# HM-ES-TX-WM_IEC_v1p0.net
KiCad netlist of a schematic drawn in EAGLE
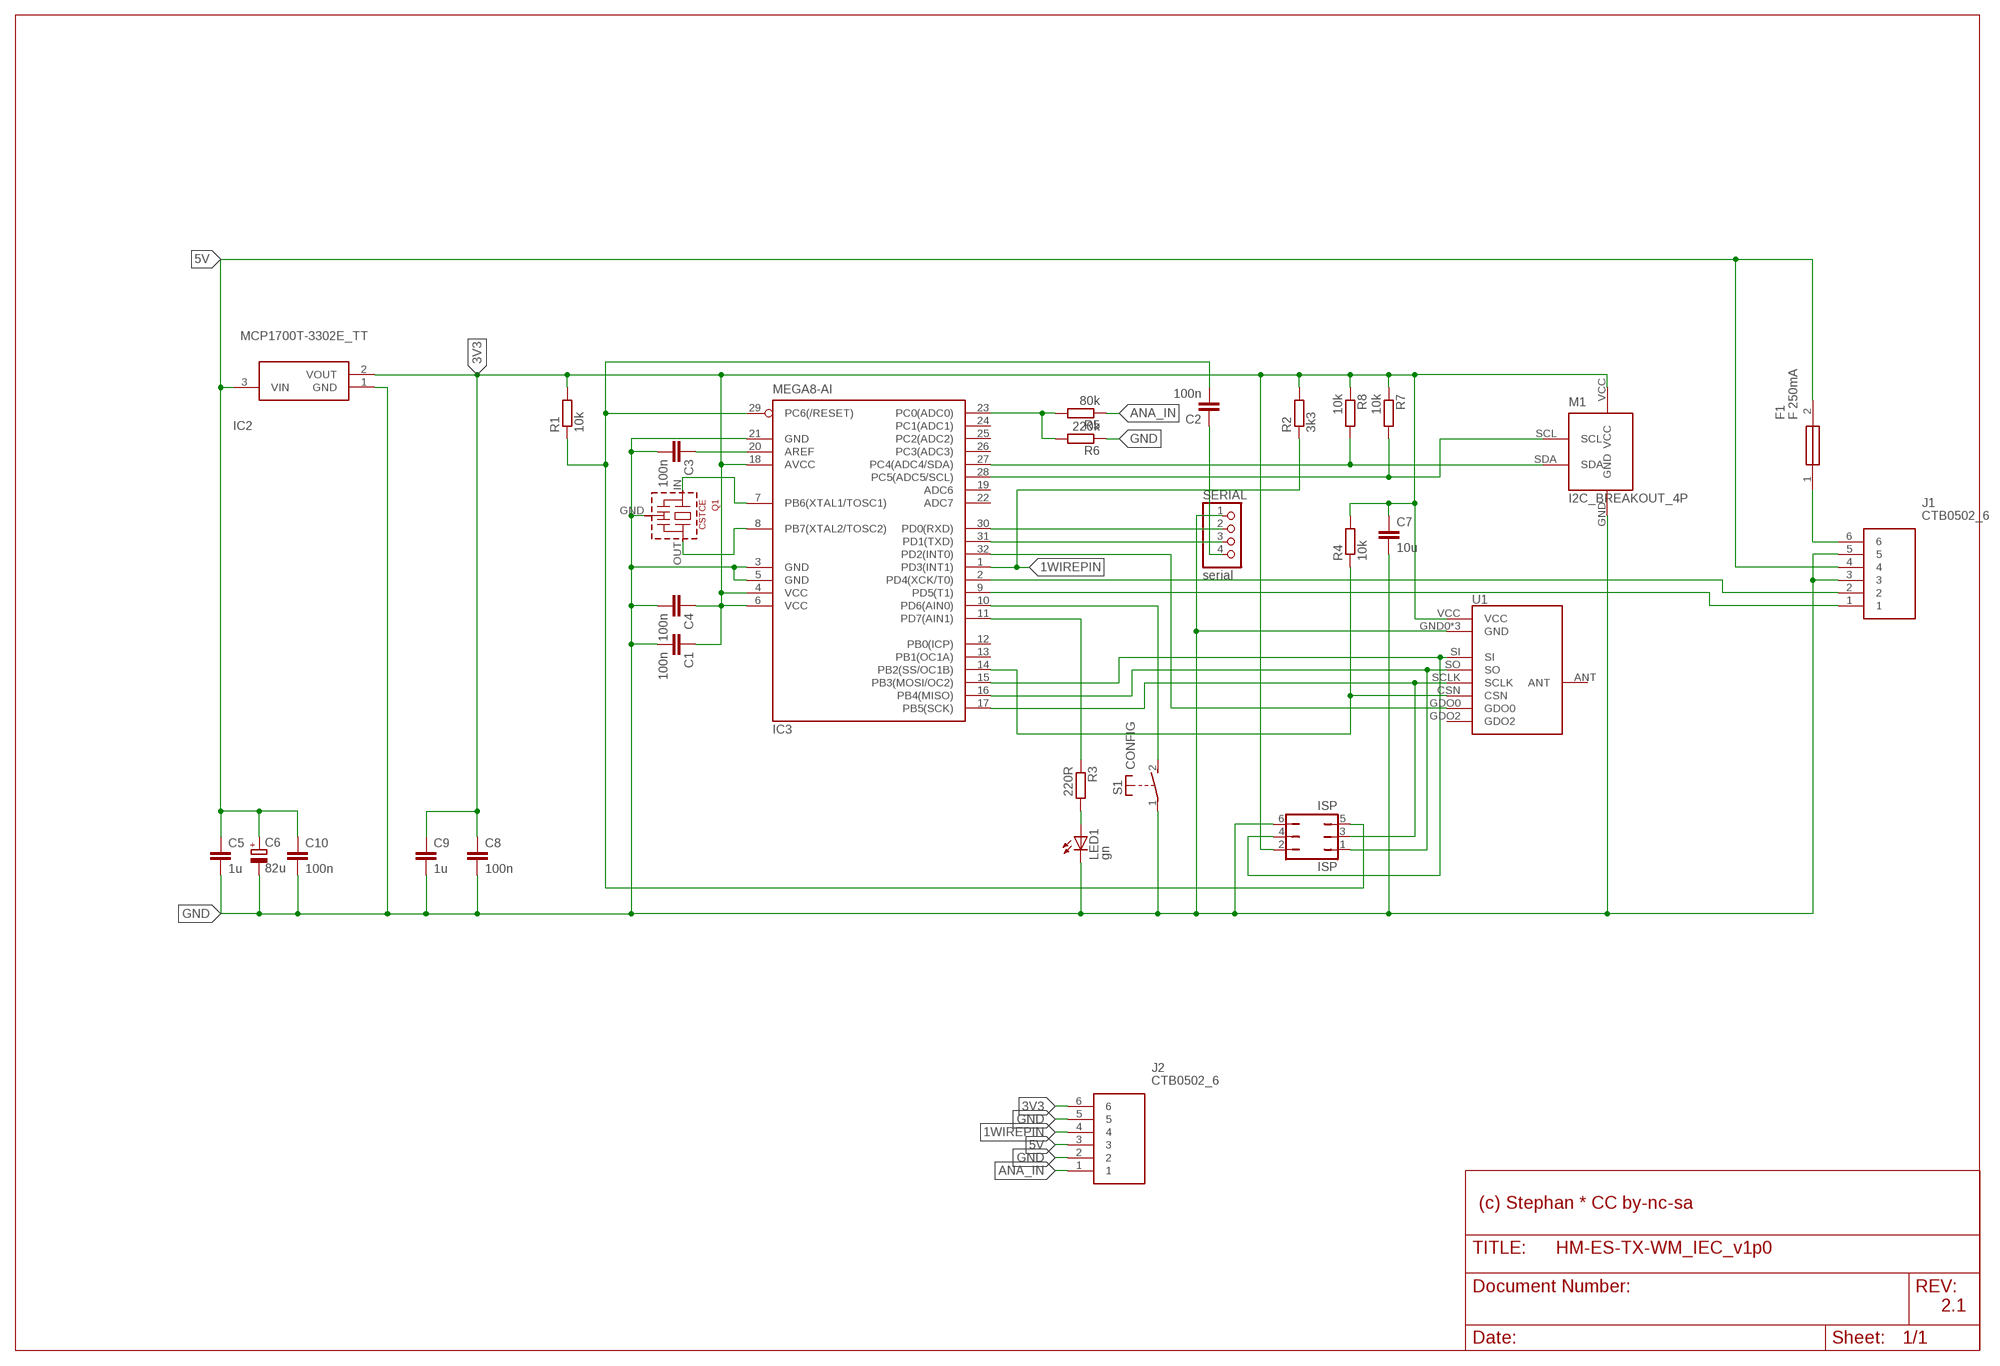
[diagram p0: schematic, sheet 1]

(export (version "E")
  (design (tool "Eeschema 10.0.6"))
  (components
    (comp (ref "C1")
      (value "100n")
      (footprint "eagle-import:C0805K")
      (libsource (lib "eagle-import") (part "C-EUC0805K"))
    )
    (comp (ref "C2")
      (value "100n")
      (footprint "eagle-import:C0805K")
      (libsource (lib "eagle-import") (part "C-EUC0805K"))
    )
    (comp (ref "C3")
      (value "100n")
      (footprint "eagle-import:C0805K")
      (libsource (lib "eagle-import") (part "C-EUC0805K"))
    )
    (comp (ref "C4")
      (value "100n")
      (footprint "eagle-import:C0805K")
      (libsource (lib "eagle-import") (part "C-EUC0805K"))
    )
    (comp (ref "C5")
      (value "1u")
      (footprint "eagle-import:C0805K")
      (libsource (lib "eagle-import") (part "C-EUC0805K"))
    )
    (comp (ref "C6")
      (value "82u")
      (footprint "eagle-import:SANYO-OSCON_SMD_C6")
      (libsource (lib "eagle-import") (part "CPOL-EUSANYO_SMD_C6"))
    )
    (comp (ref "C7")
      (value "10u")
      (footprint "eagle-import:C0805K")
      (libsource (lib "eagle-import") (part "C-EUC0805K"))
    )
    (comp (ref "C8")
      (value "100n")
      (footprint "eagle-import:C0805K")
      (libsource (lib "eagle-import") (part "C-EUC0805K"))
    )
    (comp (ref "C9")
      (value "1u")
      (footprint "eagle-import:C0805K")
      (libsource (lib "eagle-import") (part "C-EUC0805K"))
    )
    (comp (ref "C10")
      (value "100n")
      (footprint "eagle-import:C0805K")
      (libsource (lib "eagle-import") (part "C-EUC0805K"))
    )
    (comp (ref "F1")
      (value "F 250mA")
      (footprint "eagle-import:FUSC6125X279N")
      (fields (field (name "ARROW_PART_NUMBER") "0679H1000-05"))
      (libsource (lib "eagle-import") (part "0679H1000-05"))
    )
    (comp (ref "IC2")
      (value "MCP1700T-3302E_TT")
      (footprint "eagle-import:SOT95P237X112-3N")
      (fields
        (field (name "ARROW_PART_NUMBER") "MCP1700T-5002E/TT")
        (field (name "MOUSER_PART_NUMBER") "579-MCP1700T5002E/TT")
      )
      (libsource (lib "eagle-import") (part "MCP1700T-5002E_TT"))
    )
    (comp (ref "IC3")
      (value "MEGA8-AI")
      (footprint "eagle-import:TQFP32-08")
      (fields (field (name "MPN") "ATMEGA8-16AU"))
      (libsource (lib "eagle-import") (part "MEGA8-AI"))
    )
    (comp (ref "ISP")
      (value "ISP")
      (footprint "eagle-import:JP3Q")
      (libsource (lib "eagle-import") (part "JP3Q"))
    )
    (comp (ref "J1")
      (value "CTB0502_6")
      (footprint "eagle-import:CTB05026")
      (fields (field (name "MANUFACTURER_PART_NUMBER") "CTB0502/6"))
      (libsource (lib "eagle-import") (part "CTB0502_6"))
    )
    (comp (ref "J2")
      (value "CTB0502_6")
      (footprint "eagle-import:CTB05026")
      (fields (field (name "MANUFACTURER_PART_NUMBER") "CTB0502/6"))
      (libsource (lib "eagle-import") (part "CTB0502_6"))
    )
    (comp (ref "LED1")
      (value "gn")
      (footprint "eagle-import:CHIPLED_0805")
      (libsource (lib "eagle-import") (part "LEDCHIPLED_0805"))
    )
    (comp (ref "M1")
      (value "I2C_BREAKOUT_4P")
      (footprint "eagle-import:I2C_BREAKOUT_4P")
      (libsource (lib "eagle-import") (part "I2C_BREAKOUT_4P"))
    )
    (comp (ref "Q1")
      (value "CSTCE")
      (footprint "eagle-import:CSTCE")
      (libsource (lib "eagle-import") (part "CSTCE"))
    )
    (comp (ref "R1")
      (value "10k")
      (footprint "eagle-import:R0805W")
      (libsource (lib "eagle-import") (part "R-EU_R0805W"))
    )
    (comp (ref "R2")
      (value "3k3")
      (footprint "eagle-import:R0805W")
      (libsource (lib "eagle-import") (part "R-EU_R0805W"))
    )
    (comp (ref "R3")
      (value "220R")
      (footprint "eagle-import:R0805W")
      (libsource (lib "eagle-import") (part "R-EU_R0805W"))
    )
    (comp (ref "R4")
      (value "10k")
      (footprint "eagle-import:R0805W")
      (libsource (lib "eagle-import") (part "R-EU_R0805W"))
    )
    (comp (ref "R5")
      (value "80k")
      (footprint "eagle-import:R0805W")
      (libsource (lib "eagle-import") (part "R-EU_R0805W"))
    )
    (comp (ref "R6")
      (value "220k")
      (footprint "eagle-import:R0805W")
      (libsource (lib "eagle-import") (part "R-EU_R0805W"))
    )
    (comp (ref "R7")
      (value "10k")
      (footprint "eagle-import:R0805W")
      (libsource (lib "eagle-import") (part "R-EU_R0805W"))
    )
    (comp (ref "R8")
      (value "10k")
      (footprint "eagle-import:R0805W")
      (libsource (lib "eagle-import") (part "R-EU_R0805W"))
    )
    (comp (ref "S1")
      (value "CONFIG")
      (footprint "eagle-import:SMDSWITCH6X4")
      (libsource (lib "eagle-import") (part "SMDSWITCH6X4"))
    )
    (comp (ref "SERIAL")
      (value "serial")
      (footprint "eagle-import:1X04")
      (libsource (lib "eagle-import") (part "PINHD-1X4"))
    )
    (comp (ref "U1")
      (value "CC1101SMD")
      (footprint "eagle-import:CC1101-SMD")
      (libsource (lib "eagle-import") (part "CC1101SMD"))
    )
  )
  (nets
    (net (code "1") (name "1WIREPIN") (class "Default")
      (node (ref "IC3") (pin "1") (pinfunction "PD3(INT1)_1") (pintype "bidirectional"))
      (node (ref "J2") (pin "4") (pinfunction "4_4") (pintype "bidirectional"))
      (node (ref "R2") (pin "1") (pinfunction "1_1") (pintype "passive"))
    )
    (net (code "2") (name "3V3") (class "Default")
      (node (ref "C1") (pin "1") (pinfunction "1_1") (pintype "passive"))
      (node (ref "C4") (pin "1") (pinfunction "1_1") (pintype "passive"))
      (node (ref "C7") (pin "1") (pinfunction "1_1") (pintype "passive"))
      (node (ref "C8") (pin "1") (pinfunction "1_1") (pintype "passive"))
      (node (ref "C9") (pin "1") (pinfunction "1_1") (pintype "passive"))
      (node (ref "IC2") (pin "2") (pinfunction "VOUT_2") (pintype "bidirectional"))
      (node (ref "IC3") (pin "18") (pinfunction "AVCC_18") (pintype "power_in"))
      (node (ref "IC3") (pin "4") (pinfunction "VCC_4") (pintype "power_in"))
      (node (ref "IC3") (pin "6") (pinfunction "VCC_6") (pintype "power_in"))
      (node (ref "ISP") (pin "2") (pinfunction "2_2") (pintype "passive"))
      (node (ref "J2") (pin "6") (pinfunction "6_6") (pintype "bidirectional"))
      (node (ref "M1") (pin "VCC") (pinfunction "VCC_VCC") (pintype "power_in"))
      (node (ref "R1") (pin "2") (pinfunction "2_2") (pintype "passive"))
      (node (ref "R2") (pin "2") (pinfunction "2_2") (pintype "passive"))
      (node (ref "R4") (pin "2") (pinfunction "2_2") (pintype "passive"))
      (node (ref "R7") (pin "1") (pinfunction "1_1") (pintype "passive"))
      (node (ref "R8") (pin "1") (pinfunction "1_1") (pintype "passive"))
      (node (ref "U1") (pin "VCC") (pinfunction "VCC_VCC") (pintype "power_in"))
    )
    (net (code "3") (name "5V") (class "Default")
      (node (ref "C10") (pin "1") (pinfunction "1_1") (pintype "passive"))
      (node (ref "C5") (pin "1") (pinfunction "1_1") (pintype "passive"))
      (node (ref "C6") (pin "+") (pinfunction "+_+") (pintype "passive"))
      (node (ref "F1") (pin "2") (pinfunction "2_2") (pintype "bidirectional"))
      (node (ref "IC2") (pin "3") (pinfunction "VIN_3") (pintype "bidirectional"))
      (node (ref "J1") (pin "4") (pinfunction "4_4") (pintype "bidirectional"))
      (node (ref "J2") (pin "3") (pinfunction "3_3") (pintype "bidirectional"))
    )
    (net (code "4") (name "ANA_IN") (class "Default")
      (node (ref "J2") (pin "1") (pinfunction "1_1") (pintype "bidirectional"))
      (node (ref "R5") (pin "1") (pinfunction "1_1") (pintype "passive"))
    )
    (net (code "5") (name "GND") (class "Default")
      (node (ref "C1") (pin "2") (pinfunction "2_2") (pintype "passive"))
      (node (ref "C10") (pin "2") (pinfunction "2_2") (pintype "passive"))
      (node (ref "C3") (pin "2") (pinfunction "2_2") (pintype "passive"))
      (node (ref "C4") (pin "2") (pinfunction "2_2") (pintype "passive"))
      (node (ref "C5") (pin "2") (pinfunction "2_2") (pintype "passive"))
      (node (ref "C6") (pin "-") (pinfunction "-_-") (pintype "passive"))
      (node (ref "C7") (pin "2") (pinfunction "2_2") (pintype "passive"))
      (node (ref "C8") (pin "2") (pinfunction "2_2") (pintype "passive"))
      (node (ref "C9") (pin "2") (pinfunction "2_2") (pintype "passive"))
      (node (ref "IC2") (pin "1") (pinfunction "GND_1") (pintype "bidirectional"))
      (node (ref "IC3") (pin "21") (pinfunction "GND_21") (pintype "power_in"))
      (node (ref "IC3") (pin "3") (pinfunction "GND_3") (pintype "power_in"))
      (node (ref "IC3") (pin "5") (pinfunction "GND_5") (pintype "power_in"))
      (node (ref "ISP") (pin "6") (pinfunction "6_6") (pintype "passive"))
      (node (ref "J1") (pin "3") (pinfunction "3_3") (pintype "bidirectional"))
      (node (ref "J1") (pin "5") (pinfunction "5_5") (pintype "bidirectional"))
      (node (ref "J2") (pin "2") (pinfunction "2_2") (pintype "bidirectional"))
      (node (ref "J2") (pin "5") (pinfunction "5_5") (pintype "bidirectional"))
      (node (ref "LED1") (pin "C") (pinfunction "C_C") (pintype "passive"))
      (node (ref "M1") (pin "GND") (pinfunction "GND_GND") (pintype "power_in"))
      (node (ref "Q1") (pin "GND") (pinfunction "GND_GND") (pintype "power_in"))
      (node (ref "R6") (pin "1") (pinfunction "1_1") (pintype "passive"))
      (node (ref "S1") (pin "1") (pinfunction "P_1") (pintype "passive"))
      (node (ref "SERIAL") (pin "1") (pinfunction "1_1") (pintype "passive"))
      (node (ref "U1") (pin "GND0") (pinfunction "GND_GND0") (pintype "power_in"))
      (node (ref "U1") (pin "GND1") (pinfunction "GND_GND1") (pintype "power_in"))
      (node (ref "U1") (pin "GND2") (pinfunction "GND_GND2") (pintype "power_in"))
    )
    (net (code "6") (name "Net-(C2-Pad1)") (class "Default")
      (node (ref "C2") (pin "1") (pinfunction "1_1") (pintype "passive"))
      (node (ref "SERIAL") (pin "4") (pinfunction "4_4") (pintype "passive"))
    )
    (net (code "7") (name "Net-(F1-Pad1)") (class "Default")
      (node (ref "F1") (pin "1") (pinfunction "1_1") (pintype "bidirectional"))
      (node (ref "J1") (pin "6") (pinfunction "6_6") (pintype "bidirectional"))
    )
    (net (code "8") (name "Net-(IC3-AREF)") (class "Default")
      (node (ref "C3") (pin "1") (pinfunction "1_1") (pintype "passive"))
      (node (ref "IC3") (pin "20") (pinfunction "AREF_20") (pintype "passive"))
    )
    (net (code "9") (name "Net-(IC3-PB2(SS{slash}OC1B))") (class "Default")
      (node (ref "IC3") (pin "14") (pinfunction "PB2(SS/OC1B)_14") (pintype "bidirectional"))
      (node (ref "R4") (pin "1") (pinfunction "1_1") (pintype "passive"))
      (node (ref "U1") (pin "CSN") (pinfunction "CSN_CSN") (pintype "bidirectional"))
    )
    (net (code "10") (name "Net-(IC3-PB3(MOSI{slash}OC2))") (class "Default")
      (node (ref "IC3") (pin "15") (pinfunction "PB3(MOSI/OC2)_15") (pintype "bidirectional"))
      (node (ref "ISP") (pin "4") (pinfunction "4_4") (pintype "passive"))
      (node (ref "U1") (pin "SI") (pinfunction "SI_SI") (pintype "input"))
    )
    (net (code "11") (name "Net-(IC3-PB4(MISO))") (class "Default")
      (node (ref "IC3") (pin "16") (pinfunction "PB4(MISO)_16") (pintype "bidirectional"))
      (node (ref "ISP") (pin "1") (pinfunction "1_1") (pintype "passive"))
      (node (ref "U1") (pin "SO") (pinfunction "SO_SO") (pintype "output"))
    )
    (net (code "12") (name "Net-(IC3-PB5(SCK))") (class "Default")
      (node (ref "IC3") (pin "17") (pinfunction "PB5(SCK)_17") (pintype "bidirectional"))
      (node (ref "ISP") (pin "3") (pinfunction "3_3") (pintype "passive"))
      (node (ref "U1") (pin "SCLK") (pinfunction "SCLK_SCLK") (pintype "input"))
    )
    (net (code "13") (name "Net-(IC3-PB6(XTAL1{slash}TOSC1))") (class "Default")
      (node (ref "IC3") (pin "7") (pinfunction "PB6(XTAL1/TOSC1)_7") (pintype "bidirectional"))
      (node (ref "Q1") (pin "IN") (pinfunction "IN_IN") (pintype "input"))
    )
    (net (code "14") (name "Net-(IC3-PB7(XTAL2{slash}TOSC2))") (class "Default")
      (node (ref "IC3") (pin "8") (pinfunction "PB7(XTAL2/TOSC2)_8") (pintype "bidirectional"))
      (node (ref "Q1") (pin "OUT") (pinfunction "OUT_OUT") (pintype "output"))
    )
    (net (code "15") (name "Net-(IC3-PC0(ADC0))") (class "Default")
      (node (ref "IC3") (pin "23") (pinfunction "PC0(ADC0)_23") (pintype "bidirectional"))
      (node (ref "R5") (pin "2") (pinfunction "2_2") (pintype "passive"))
      (node (ref "R6") (pin "2") (pinfunction "2_2") (pintype "passive"))
    )
    (net (code "16") (name "Net-(IC3-PC4(ADC4{slash}SDA))") (class "Default")
      (node (ref "IC3") (pin "27") (pinfunction "PC4(ADC4/SDA)_27") (pintype "bidirectional"))
      (node (ref "M1") (pin "SDA") (pinfunction "SDA_SDA") (pintype "bidirectional"))
      (node (ref "R8") (pin "2") (pinfunction "2_2") (pintype "passive"))
    )
    (net (code "17") (name "Net-(IC3-PC5(ADC5{slash}SCL))") (class "Default")
      (node (ref "IC3") (pin "28") (pinfunction "PC5(ADC5/SCL)_28") (pintype "bidirectional"))
      (node (ref "M1") (pin "SCL") (pinfunction "SCL_SCL") (pintype "bidirectional"))
      (node (ref "R7") (pin "2") (pinfunction "2_2") (pintype "passive"))
    )
    (net (code "18") (name "Net-(IC3-PC6({slash}RESET))") (class "Default")
      (node (ref "C2") (pin "2") (pinfunction "2_2") (pintype "passive"))
      (node (ref "IC3") (pin "29") (pinfunction "PC6(/RESET)_29") (pintype "bidirectional"))
      (node (ref "ISP") (pin "5") (pinfunction "5_5") (pintype "passive"))
      (node (ref "R1") (pin "1") (pinfunction "1_1") (pintype "passive"))
    )
    (net (code "19") (name "Net-(IC3-PD0(RXD))") (class "Default")
      (node (ref "IC3") (pin "30") (pinfunction "PD0(RXD)_30") (pintype "bidirectional"))
      (node (ref "SERIAL") (pin "2") (pinfunction "2_2") (pintype "passive"))
    )
    (net (code "20") (name "Net-(IC3-PD1(TXD))") (class "Default")
      (node (ref "IC3") (pin "31") (pinfunction "PD1(TXD)_31") (pintype "bidirectional"))
      (node (ref "SERIAL") (pin "3") (pinfunction "3_3") (pintype "passive"))
    )
    (net (code "21") (name "Net-(IC3-PD2(INT0))") (class "Default")
      (node (ref "IC3") (pin "32") (pinfunction "PD2(INT0)_32") (pintype "bidirectional"))
      (node (ref "U1") (pin "GDO0") (pinfunction "GDO0_GDO0") (pintype "output"))
    )
    (net (code "22") (name "Net-(IC3-PD4(XCK{slash}T0))") (class "Default")
      (node (ref "IC3") (pin "2") (pinfunction "PD4(XCK/T0)_2") (pintype "bidirectional"))
      (node (ref "J1") (pin "2") (pinfunction "2_2") (pintype "bidirectional"))
    )
    (net (code "23") (name "Net-(IC3-PD5(T1))") (class "Default")
      (node (ref "IC3") (pin "9") (pinfunction "PD5(T1)_9") (pintype "bidirectional"))
      (node (ref "J1") (pin "1") (pinfunction "1_1") (pintype "bidirectional"))
    )
    (net (code "24") (name "Net-(IC3-PD6(AIN0))") (class "Default")
      (node (ref "IC3") (pin "10") (pinfunction "PD6(AIN0)_10") (pintype "bidirectional"))
      (node (ref "S1") (pin "2") (pinfunction "S_2") (pintype "passive"))
    )
    (net (code "25") (name "Net-(IC3-PD7(AIN1))") (class "Default")
      (node (ref "IC3") (pin "11") (pinfunction "PD7(AIN1)_11") (pintype "bidirectional"))
      (node (ref "R3") (pin "1") (pinfunction "1_1") (pintype "passive"))
    )
    (net (code "26") (name "Net-(LED1-PadA)") (class "Default")
      (node (ref "LED1") (pin "A") (pinfunction "A_A") (pintype "passive"))
      (node (ref "R3") (pin "2") (pinfunction "2_2") (pintype "passive"))
    )
    (net (code "27") (name "unconnected-(IC3-ADC6-Pad19)") (class "Default")
      (node (ref "IC3") (pin "19") (pinfunction "ADC6_19") (pintype "bidirectional"))
    )
    (net (code "28") (name "unconnected-(IC3-ADC7-Pad22)") (class "Default")
      (node (ref "IC3") (pin "22") (pinfunction "ADC7_22") (pintype "bidirectional"))
    )
    (net (code "29") (name "unconnected-(IC3-PB0(ICP)-Pad12)") (class "Default")
      (node (ref "IC3") (pin "12") (pinfunction "PB0(ICP)_12") (pintype "bidirectional"))
    )
    (net (code "30") (name "unconnected-(IC3-PB1(OC1A)-Pad13)") (class "Default")
      (node (ref "IC3") (pin "13") (pinfunction "PB1(OC1A)_13") (pintype "bidirectional"))
    )
    (net (code "31") (name "unconnected-(IC3-PC1(ADC1)-Pad24)") (class "Default")
      (node (ref "IC3") (pin "24") (pinfunction "PC1(ADC1)_24") (pintype "bidirectional"))
    )
    (net (code "32") (name "unconnected-(IC3-PC2(ADC2)-Pad25)") (class "Default")
      (node (ref "IC3") (pin "25") (pinfunction "PC2(ADC2)_25") (pintype "bidirectional"))
    )
    (net (code "33") (name "unconnected-(IC3-PC3(ADC3)-Pad26)") (class "Default")
      (node (ref "IC3") (pin "26") (pinfunction "PC3(ADC3)_26") (pintype "bidirectional"))
    )
    (net (code "34") (name "unconnected-(U1-PadANT)") (class "Default")
      (node (ref "U1") (pin "ANT") (pinfunction "ANT_ANT") (pintype "input"))
    )
    (net (code "35") (name "unconnected-(U1-PadGDO2)") (class "Default")
      (node (ref "U1") (pin "GDO2") (pinfunction "GDO2_GDO2") (pintype "output"))
    )
  )
)
